# Production_Rev_A.net
KiCad netlist of a schematic drawn in EAGLE
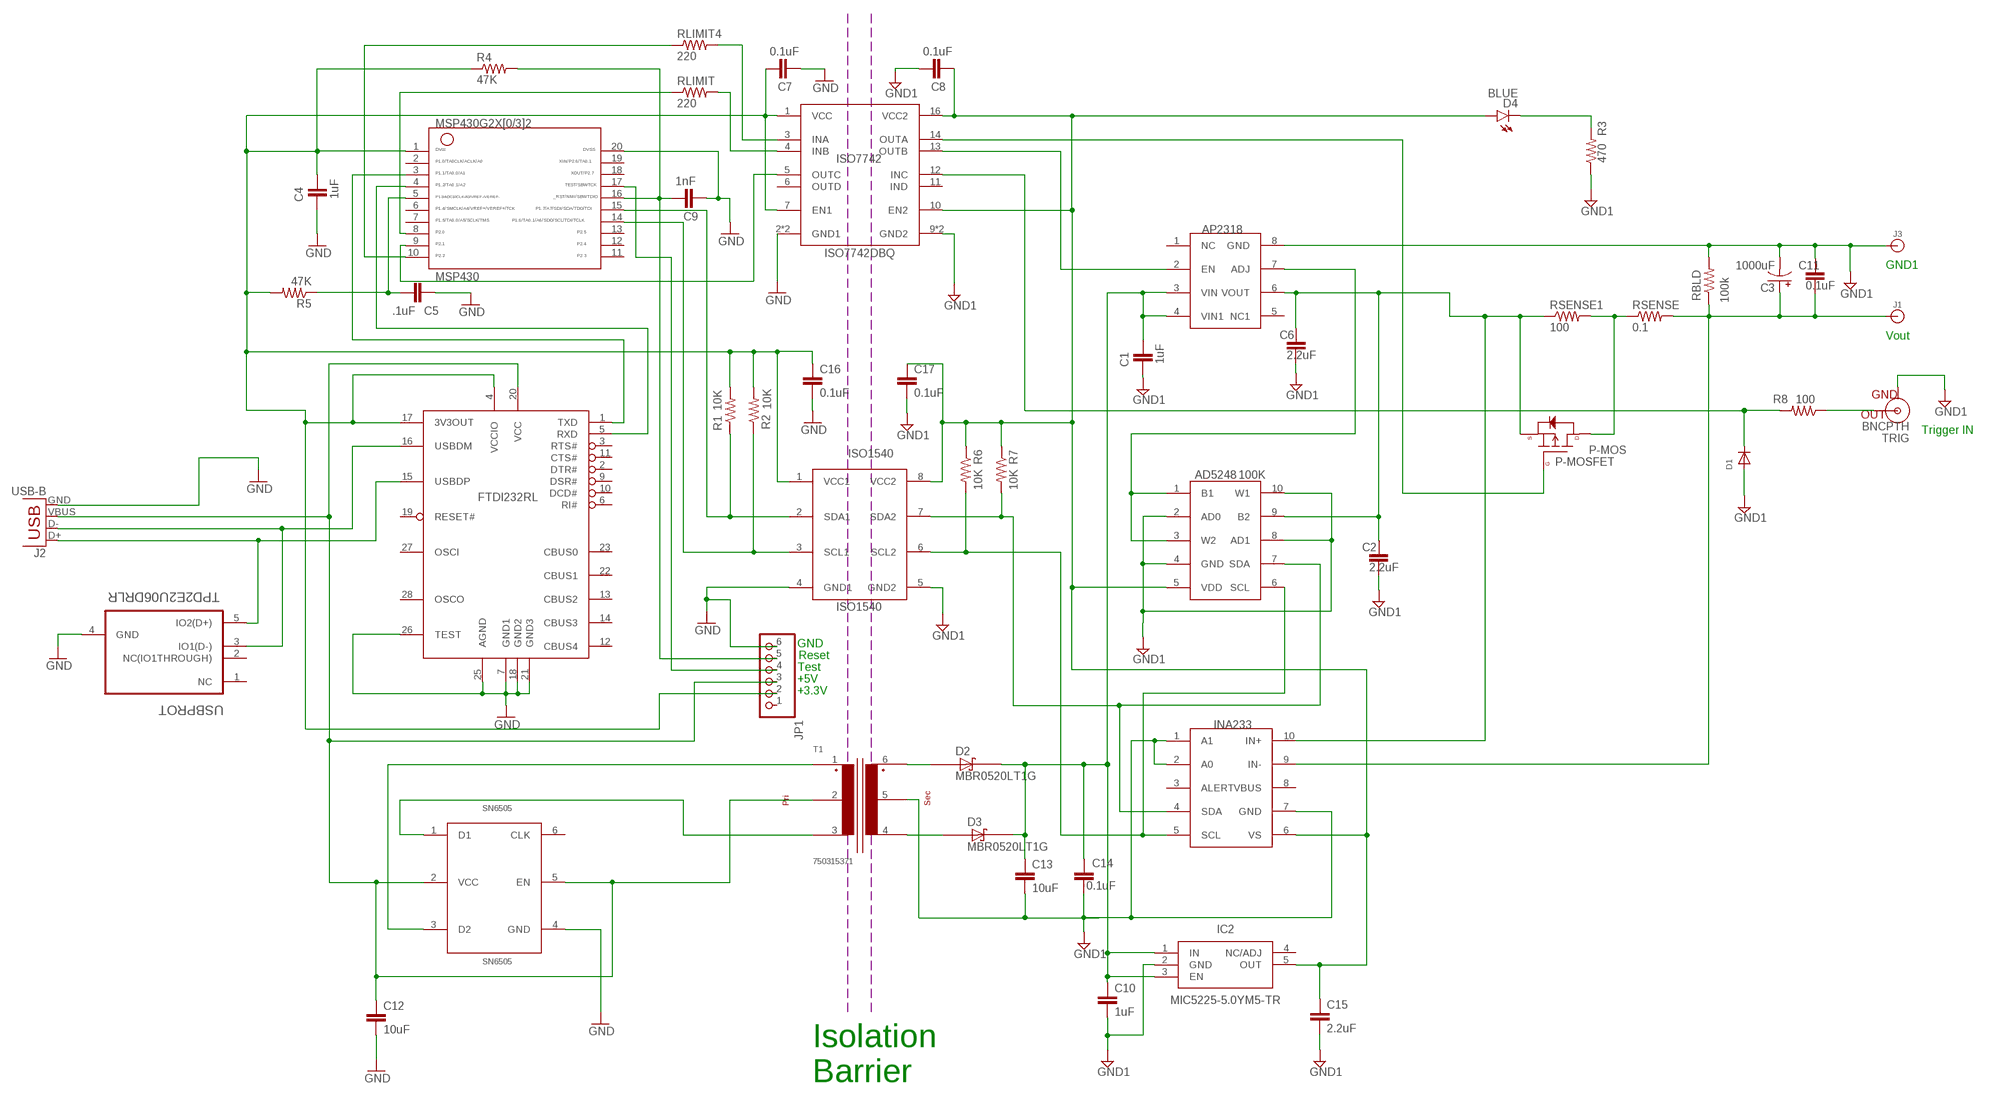
[diagram p0: schematic, sheet 1]

(export (version "E")
  (design (tool "Eeschema 10.0.6"))
  (components
    (comp (ref "AD5248")
      (value "100K")
      (footprint "eagle-import:MSOP-10")
      (libsource (lib "eagle-import") (part "AD5248"))
    )
    (comp (ref "AP2318")
      (value "AP2318")
      (footprint "eagle-import:SOIC-8")
      (libsource (lib "eagle-import") (part "AP2318"))
    )
    (comp (ref "C1")
      (value "1uF")
      (footprint "eagle-import:1206")
      (libsource (lib "eagle-import") (part "CAP1206"))
    )
    (comp (ref "C2")
      (value "2.2uF")
      (footprint "eagle-import:1206")
      (libsource (lib "eagle-import") (part "CAP1206"))
    )
    (comp (ref "C3")
      (value "1000uF")
      (footprint "eagle-import:PANASONIC_F")
      (libsource (lib "eagle-import") (part "CPOL-USF"))
    )
    (comp (ref "C4")
      (value "1uF")
      (footprint "eagle-import:1206")
      (libsource (lib "eagle-import") (part "CAP1206"))
    )
    (comp (ref "C5")
      (value ".1uF")
      (footprint "eagle-import:1206")
      (libsource (lib "eagle-import") (part "CAP1206"))
    )
    (comp (ref "C6")
      (value "2.2uF")
      (footprint "eagle-import:1206")
      (libsource (lib "eagle-import") (part "CAP1206"))
    )
    (comp (ref "C7")
      (value "0.1uF")
      (footprint "eagle-import:1206")
      (libsource (lib "eagle-import") (part "CAP1206"))
    )
    (comp (ref "C8")
      (value "0.1uF")
      (footprint "eagle-import:1206")
      (libsource (lib "eagle-import") (part "CAP1206"))
    )
    (comp (ref "C9")
      (value "1nF")
      (footprint "eagle-import:1206")
      (libsource (lib "eagle-import") (part "CAP1206"))
    )
    (comp (ref "C10")
      (value "1uF")
      (footprint "eagle-import:1206")
      (libsource (lib "eagle-import") (part "CAP1206"))
    )
    (comp (ref "C11")
      (value "0.1uF")
      (footprint "eagle-import:1206")
      (libsource (lib "eagle-import") (part "CAP1206"))
    )
    (comp (ref "C12")
      (value "10uF")
      (footprint "eagle-import:1206")
      (libsource (lib "eagle-import") (part "CAP1206"))
    )
    (comp (ref "C13")
      (value "10uF")
      (footprint "eagle-import:1206")
      (libsource (lib "eagle-import") (part "CAP1206"))
    )
    (comp (ref "C14")
      (value "0.1uF")
      (footprint "eagle-import:1206")
      (libsource (lib "eagle-import") (part "CAP1206"))
    )
    (comp (ref "C15")
      (value "2.2uF")
      (footprint "eagle-import:1206")
      (libsource (lib "eagle-import") (part "CAP1206"))
    )
    (comp (ref "C16")
      (value "0.1uF")
      (footprint "eagle-import:1206")
      (libsource (lib "eagle-import") (part "CAP1206"))
    )
    (comp (ref "C17")
      (value "0.1uF")
      (footprint "eagle-import:1206")
      (libsource (lib "eagle-import") (part "CAP1206"))
    )
    (comp (ref "D1")
      (value "DIODESOD-123")
      (footprint "eagle-import:SOD-123")
      (libsource (lib "eagle-import") (part "DIODESOD-123"))
    )
    (comp (ref "D2")
      (value "MBR0520LT1G")
      (footprint "eagle-import:SOD3716X117(SOD-123)")
      (fields (field (name "MF") "ON Semiconductor"))
      (libsource (lib "eagle-import") (part "MBR0520LT1G"))
    )
    (comp (ref "D3")
      (value "MBR0520LT1G")
      (footprint "eagle-import:SOD3716X117(SOD-123)")
      (fields (field (name "MF") "ON Semiconductor"))
      (libsource (lib "eagle-import") (part "MBR0520LT1G"))
    )
    (comp (ref "D4")
      (value "BLUE")
      (footprint "eagle-import:LED-1206")
      (libsource (lib "eagle-import") (part "LED-BLUE1206"))
    )
    (comp (ref "FTDI232RL")
      (value "FT232RL")
      (footprint "eagle-import:SSOP28DB")
      (libsource (lib "eagle-import") (part "FT232RL"))
    )
    (comp (ref "IC2")
      (value "MIC5225-5.0YM5-TR")
      (footprint "eagle-import:SOT95P280X130-5N")
      (fields (field (name "MF") "Microchip"))
      (libsource (lib "eagle-import") (part "MIC5225-5.0YM5-TR"))
    )
    (comp (ref "INA233")
      (value "INA233")
      (footprint "eagle-import:VSSOP-10")
      (libsource (lib "eagle-import") (part "INA233"))
    )
    (comp (ref "ISO1540")
      (value "ISO1540")
      (footprint "eagle-import:SOIC127P600X175-8N")
      (libsource (lib "eagle-import") (part "ISO1540"))
    )
    (comp (ref "ISO7742")
      (value "ISO7742DBQ")
      (footprint "eagle-import:SOP63P599X175-16N")
      (fields (field (name "MF") "Texas Instruments"))
      (libsource (lib "eagle-import") (part "ISO7742DBQ"))
    )
    (comp (ref "J1")
      (value "BANANA_CONN")
      (footprint "eagle-import:BANANA_CONN")
      (libsource (lib "eagle-import") (part "BANANA_CONN"))
    )
    (comp (ref "J2")
      (value "USB-B")
      (footprint "eagle-import:USB-B-PTH")
      (libsource (lib "eagle-import") (part "USBPTH"))
    )
    (comp (ref "J3")
      (value "BANANA_CONN")
      (footprint "eagle-import:BANANA_CONN")
      (libsource (lib "eagle-import") (part "BANANA_CONN"))
    )
    (comp (ref "JP1")
      (value "PINHD-1X6")
      (footprint "eagle-import:1X06")
      (libsource (lib "eagle-import") (part "PINHD-1X6"))
    )
    (comp (ref "MSP430")
      (value "MSP430")
      (footprint "eagle-import:PW20")
      (libsource (lib "eagle-import") (part "G2X[0/3]2---PW20"))
    )
    (comp (ref "P-MOS")
      (value "P-MOSFET")
      (footprint "eagle-import:SOT23-3")
      (libsource (lib "eagle-import") (part "P-CHANNEL-MOSFET"))
    )
    (comp (ref "R1")
      (value "10K")
      (footprint "eagle-import:1206")
      (libsource (lib "eagle-import") (part "RESISTOR1206"))
    )
    (comp (ref "R2")
      (value "10K")
      (footprint "eagle-import:1206")
      (libsource (lib "eagle-import") (part "RESISTOR1206"))
    )
    (comp (ref "R3")
      (value "470")
      (footprint "eagle-import:1206")
      (libsource (lib "eagle-import") (part "RESISTOR1206"))
    )
    (comp (ref "R4")
      (value "47K")
      (footprint "eagle-import:1206")
      (libsource (lib "eagle-import") (part "RESISTOR1206"))
    )
    (comp (ref "R5")
      (value "47K")
      (footprint "eagle-import:1206")
      (libsource (lib "eagle-import") (part "RESISTOR1206"))
    )
    (comp (ref "R6")
      (value "10K")
      (footprint "eagle-import:1206")
      (libsource (lib "eagle-import") (part "RESISTOR1206"))
    )
    (comp (ref "R7")
      (value "10K")
      (footprint "eagle-import:1206")
      (libsource (lib "eagle-import") (part "RESISTOR1206"))
    )
    (comp (ref "R8")
      (value "100")
      (footprint "eagle-import:1206")
      (libsource (lib "eagle-import") (part "RESISTOR1206"))
    )
    (comp (ref "RBLD")
      (value "100k")
      (footprint "eagle-import:1206")
      (libsource (lib "eagle-import") (part "RESISTOR1206"))
    )
    (comp (ref "RLIMIT")
      (value "220")
      (footprint "eagle-import:1206")
      (libsource (lib "eagle-import") (part "SparkFun-Resistors_RESISTOR1206"))
    )
    (comp (ref "RLIMIT4")
      (value "220")
      (footprint "eagle-import:1206")
      (libsource (lib "eagle-import") (part "SparkFun-Resistors_RESISTOR1206"))
    )
    (comp (ref "RSENSE")
      (value "0.1")
      (footprint "eagle-import:1206")
      (libsource (lib "eagle-import") (part "SparkFun-Resistors_RESISTOR1206"))
    )
    (comp (ref "RSENSE1")
      (value "100")
      (footprint "eagle-import:1206")
      (libsource (lib "eagle-import") (part "SparkFun-Resistors_RESISTOR1206"))
    )
    (comp (ref "SN6505")
      (value "SN6505")
      (footprint "eagle-import:SOT95P280X145-6N")
      (libsource (lib "eagle-import") (part "SN6505"))
    )
    (comp (ref "T1")
      (value "750315371")
      (footprint "eagle-import:TOR-6P-HT4_SMT_6PIN_(1201)")
      (fields (field (name "MF") "Wurth Electronics"))
      (libsource (lib "eagle-import") (part "750315371"))
    )
    (comp (ref "TRIG")
      (value "BNCPTH")
      (footprint "eagle-import:BNC")
      (libsource (lib "eagle-import") (part "BNCPTH"))
    )
    (comp (ref "USBPROT")
      (value "TPD2E2U06DRLR")
      (footprint "eagle-import:SOT50P160X60-5N")
      (fields (field (name "MF") "Texas Instruments"))
      (libsource (lib "eagle-import") (part "TPD2E2U06DRLR"))
    )
  )
  (nets
    (net (code "1") (name "/NC") (class "Default")
      (node (ref "USBPROT") (pin "1") (pinfunction "NC_1") (pintype "power_in"))
    )
    (net (code "2") (name "GND") (class "Default")
      (node (ref "C12") (pin "2") (pinfunction "2_2") (pintype "passive"))
      (node (ref "C16") (pin "2") (pinfunction "2_2") (pintype "passive"))
      (node (ref "C4") (pin "1") (pinfunction "1_1") (pintype "passive"))
      (node (ref "C5") (pin "1") (pinfunction "1_1") (pintype "passive"))
      (node (ref "C7") (pin "1") (pinfunction "1_1") (pintype "passive"))
      (node (ref "C9") (pin "1") (pinfunction "1_1") (pintype "passive"))
      (node (ref "FTDI232RL") (pin "18") (pinfunction "GND2_18") (pintype "power_in"))
      (node (ref "FTDI232RL") (pin "21") (pinfunction "GND3_21") (pintype "power_in"))
      (node (ref "FTDI232RL") (pin "25") (pinfunction "AGND_25") (pintype "power_in"))
      (node (ref "FTDI232RL") (pin "26") (pinfunction "TEST_26") (pintype "input"))
      (node (ref "FTDI232RL") (pin "7") (pinfunction "GND1_7") (pintype "power_in"))
      (node (ref "ISO1540") (pin "4") (pinfunction "GND1_4") (pintype "bidirectional"))
      (node (ref "ISO7742") (pin "2") (pinfunction "GND1_2") (pintype "power_in"))
      (node (ref "ISO7742") (pin "8") (pinfunction "GND1_8") (pintype "power_in"))
      (node (ref "J2") (pin "GND") (pinfunction "GND_GND") (pintype "bidirectional"))
      (node (ref "JP1") (pin "6") (pinfunction "6_6") (pintype "passive"))
      (node (ref "MSP430") (pin "20") (pinfunction "20_20") (pintype "bidirectional"))
      (node (ref "SN6505") (pin "4") (pinfunction "GND_4") (pintype "bidirectional"))
      (node (ref "USBPROT") (pin "4") (pinfunction "GND_4") (pintype "passive"))
    )
    (net (code "3") (name "GND1") (class "Default")
      (node (ref "AD5248") (pin "10") (pinfunction "W1_10") (pintype "bidirectional"))
      (node (ref "AD5248") (pin "2") (pinfunction "AD0_2") (pintype "bidirectional"))
      (node (ref "AD5248") (pin "4") (pinfunction "GND_4") (pintype "bidirectional"))
      (node (ref "AD5248") (pin "8") (pinfunction "AD1_8") (pintype "bidirectional"))
      (node (ref "AP2318") (pin "8") (pinfunction "GND_8") (pintype "bidirectional"))
      (node (ref "C1") (pin "1") (pinfunction "1_1") (pintype "passive"))
      (node (ref "C10") (pin "2") (pinfunction "2_2") (pintype "passive"))
      (node (ref "C11") (pin "1") (pinfunction "1_1") (pintype "passive"))
      (node (ref "C13") (pin "2") (pinfunction "2_2") (pintype "passive"))
      (node (ref "C14") (pin "2") (pinfunction "2_2") (pintype "passive"))
      (node (ref "C15") (pin "2") (pinfunction "2_2") (pintype "passive"))
      (node (ref "C17") (pin "2") (pinfunction "2_2") (pintype "passive"))
      (node (ref "C2") (pin "2") (pinfunction "2_2") (pintype "passive"))
      (node (ref "C3") (pin "-") (pinfunction "-_-") (pintype "passive"))
      (node (ref "C6") (pin "2") (pinfunction "2_2") (pintype "passive"))
      (node (ref "C8") (pin "2") (pinfunction "2_2") (pintype "passive"))
      (node (ref "D1") (pin "A") (pinfunction "A_A") (pintype "passive"))
      (node (ref "IC2") (pin "2") (pinfunction "GND_2") (pintype "passive"))
      (node (ref "INA233") (pin "1") (pinfunction "A1_1") (pintype "bidirectional"))
      (node (ref "INA233") (pin "2") (pinfunction "A0_2") (pintype "bidirectional"))
      (node (ref "INA233") (pin "7") (pinfunction "GND_7") (pintype "bidirectional"))
      (node (ref "ISO1540") (pin "5") (pinfunction "GND2_5") (pintype "bidirectional"))
      (node (ref "ISO7742") (pin "15") (pinfunction "GND2_15") (pintype "power_in"))
      (node (ref "ISO7742") (pin "9") (pinfunction "GND2_9") (pintype "power_in"))
      (node (ref "J3") (pin "P$1") (pinfunction "1_P$1") (pintype "passive"))
      (node (ref "R3") (pin "1") (pinfunction "1_1") (pintype "passive"))
      (node (ref "RBLD") (pin "2") (pinfunction "2_2") (pintype "passive"))
      (node (ref "T1") (pin "5") (pinfunction "5_5") (pintype "passive"))
      (node (ref "TRIG") (pin "GND") (pinfunction "GND_GND") (pintype "bidirectional"))
    )
    (net (code "4") (name "Net-(AD5248-B1)") (class "Default")
      (node (ref "AD5248") (pin "1") (pinfunction "B1_1") (pintype "bidirectional"))
      (node (ref "AD5248") (pin "3") (pinfunction "W2_3") (pintype "bidirectional"))
      (node (ref "AP2318") (pin "7") (pinfunction "ADJ_7") (pintype "bidirectional"))
    )
    (net (code "5") (name "Net-(AD5248-B2)") (class "Default")
      (node (ref "AD5248") (pin "9") (pinfunction "B2_9") (pintype "bidirectional"))
      (node (ref "AP2318") (pin "6") (pinfunction "VOUT_6") (pintype "bidirectional"))
      (node (ref "C2") (pin "1") (pinfunction "1_1") (pintype "passive"))
      (node (ref "C6") (pin "1") (pinfunction "1_1") (pintype "passive"))
      (node (ref "INA233") (pin "10") (pinfunction "IN+_10") (pintype "input"))
      (node (ref "P-MOS") (pin "2") (pinfunction "S_2") (pintype "passive"))
      (node (ref "RSENSE1") (pin "1") (pinfunction "1_1") (pintype "passive"))
    )
    (net (code "6") (name "Net-(AD5248-SCL)") (class "Default")
      (node (ref "AD5248") (pin "6") (pinfunction "SCL_6") (pintype "input"))
      (node (ref "INA233") (pin "5") (pinfunction "SCL_5") (pintype "input"))
      (node (ref "ISO1540") (pin "6") (pinfunction "SCL2_6") (pintype "bidirectional"))
      (node (ref "R6") (pin "2") (pinfunction "2_2") (pintype "passive"))
    )
    (net (code "7") (name "Net-(AD5248-SDA)") (class "Default")
      (node (ref "AD5248") (pin "7") (pinfunction "SDA_7") (pintype "input"))
      (node (ref "INA233") (pin "4") (pinfunction "SDA_4") (pintype "input"))
      (node (ref "ISO1540") (pin "7") (pinfunction "SDA2_7") (pintype "bidirectional"))
      (node (ref "R7") (pin "2") (pinfunction "2_2") (pintype "passive"))
    )
    (net (code "8") (name "Net-(AD5248-VDD)") (class "Default")
      (node (ref "AD5248") (pin "5") (pinfunction "VDD_5") (pintype "power_in"))
      (node (ref "C15") (pin "1") (pinfunction "1_1") (pintype "passive"))
      (node (ref "C17") (pin "1") (pinfunction "1_1") (pintype "passive"))
      (node (ref "C8") (pin "1") (pinfunction "1_1") (pintype "passive"))
      (node (ref "D4") (pin "A") (pinfunction "A_A") (pintype "passive"))
      (node (ref "IC2") (pin "5") (pinfunction "OUT_5") (pintype "passive"))
      (node (ref "INA233") (pin "6") (pinfunction "VS_6") (pintype "power_in"))
      (node (ref "ISO1540") (pin "8") (pinfunction "VCC2_8") (pintype "bidirectional"))
      (node (ref "ISO7742") (pin "10") (pinfunction "EN2_10") (pintype "input"))
      (node (ref "ISO7742") (pin "16") (pinfunction "VCC2_16") (pintype "power_in"))
      (node (ref "R6") (pin "1") (pinfunction "1_1") (pintype "passive"))
      (node (ref "R7") (pin "1") (pinfunction "1_1") (pintype "passive"))
    )
    (net (code "9") (name "Net-(AP2318-EN)") (class "Default")
      (node (ref "AP2318") (pin "2") (pinfunction "EN_2") (pintype "bidirectional"))
      (node (ref "ISO7742") (pin "13") (pinfunction "OUTB_13") (pintype "output"))
    )
    (net (code "10") (name "Net-(AP2318-VIN)") (class "Default")
      (node (ref "AP2318") (pin "3") (pinfunction "VIN_3") (pintype "power_in"))
      (node (ref "AP2318") (pin "4") (pinfunction "VIN1_4") (pintype "power_in"))
      (node (ref "C1") (pin "2") (pinfunction "2_2") (pintype "passive"))
      (node (ref "C10") (pin "1") (pinfunction "1_1") (pintype "passive"))
      (node (ref "C13") (pin "1") (pinfunction "1_1") (pintype "passive"))
      (node (ref "C14") (pin "1") (pinfunction "1_1") (pintype "passive"))
      (node (ref "D2") (pin "1") (pinfunction "C_1") (pintype "passive"))
      (node (ref "D3") (pin "1") (pinfunction "C_1") (pintype "passive"))
      (node (ref "IC2") (pin "1") (pinfunction "IN_1") (pintype "passive"))
      (node (ref "IC2") (pin "3") (pinfunction "EN_3") (pintype "passive"))
    )
    (net (code "11") (name "Net-(C5-Pad2)") (class "Default")
      (node (ref "C5") (pin "2") (pinfunction "2_2") (pintype "passive"))
      (node (ref "MSP430") (pin "5") (pinfunction "5_5") (pintype "bidirectional"))
      (node (ref "R5") (pin "1") (pinfunction "1_1") (pintype "passive"))
    )
    (net (code "12") (name "Net-(C9-Pad2)") (class "Default")
      (node (ref "C9") (pin "2") (pinfunction "2_2") (pintype "passive"))
      (node (ref "JP1") (pin "5") (pinfunction "5_5") (pintype "passive"))
      (node (ref "MSP430") (pin "16") (pinfunction "16_16") (pintype "bidirectional"))
      (node (ref "R4") (pin "2") (pinfunction "2_2") (pintype "passive"))
    )
    (net (code "13") (name "Net-(D2-A)") (class "Default")
      (node (ref "D2") (pin "2") (pinfunction "A_2") (pintype "passive"))
      (node (ref "T1") (pin "6") (pinfunction "6_6") (pintype "passive"))
    )
    (net (code "14") (name "Net-(D3-A)") (class "Default")
      (node (ref "D3") (pin "2") (pinfunction "A_2") (pintype "passive"))
      (node (ref "T1") (pin "4") (pinfunction "4_4") (pintype "passive"))
    )
    (net (code "15") (name "Net-(D4-PadC)") (class "Default")
      (node (ref "D4") (pin "C") (pinfunction "C_C") (pintype "passive"))
      (node (ref "R3") (pin "2") (pinfunction "2_2") (pintype "passive"))
    )
    (net (code "16") (name "Net-(FTDI232RL-3V3OUT)") (class "Default")
      (node (ref "C16") (pin "1") (pinfunction "1_1") (pintype "passive"))
      (node (ref "C4") (pin "2") (pinfunction "2_2") (pintype "passive"))
      (node (ref "C7") (pin "2") (pinfunction "2_2") (pintype "passive"))
      (node (ref "FTDI232RL") (pin "17") (pinfunction "3V3OUT_17") (pintype "output"))
      (node (ref "FTDI232RL") (pin "4") (pinfunction "VCCIO_4") (pintype "power_in"))
      (node (ref "ISO1540") (pin "1") (pinfunction "VCC1_1") (pintype "bidirectional"))
      (node (ref "ISO7742") (pin "1") (pinfunction "VCC_1") (pintype "power_in"))
      (node (ref "ISO7742") (pin "7") (pinfunction "EN1_7") (pintype "input"))
      (node (ref "JP1") (pin "2") (pinfunction "2_2") (pintype "passive"))
      (node (ref "MSP430") (pin "1") (pinfunction "1_1") (pintype "bidirectional"))
      (node (ref "R1") (pin "2") (pinfunction "2_2") (pintype "passive"))
      (node (ref "R2") (pin "2") (pinfunction "2_2") (pintype "passive"))
      (node (ref "R4") (pin "1") (pinfunction "1_1") (pintype "passive"))
      (node (ref "R5") (pin "2") (pinfunction "2_2") (pintype "passive"))
    )
    (net (code "17") (name "Net-(FTDI232RL-RXD)") (class "Default")
      (node (ref "FTDI232RL") (pin "5") (pinfunction "RXD_5") (pintype "input"))
      (node (ref "MSP430") (pin "4") (pinfunction "4_4") (pintype "bidirectional"))
    )
    (net (code "18") (name "Net-(FTDI232RL-TXD)") (class "Default")
      (node (ref "FTDI232RL") (pin "1") (pinfunction "TXD_1") (pintype "output"))
      (node (ref "MSP430") (pin "3") (pinfunction "3_3") (pintype "bidirectional"))
    )
    (net (code "19") (name "Net-(FTDI232RL-USBDM)") (class "Default")
      (node (ref "FTDI232RL") (pin "16") (pinfunction "USBDM_16") (pintype "bidirectional"))
      (node (ref "J2") (pin "D-") (pinfunction "D-_D-") (pintype "bidirectional"))
      (node (ref "USBPROT") (pin "3") (pinfunction "IO1(D-)_3") (pintype "bidirectional"))
    )
    (net (code "20") (name "Net-(FTDI232RL-USBDP)") (class "Default")
      (node (ref "FTDI232RL") (pin "15") (pinfunction "USBDP_15") (pintype "bidirectional"))
      (node (ref "J2") (pin "D+") (pinfunction "D+_D+") (pintype "bidirectional"))
      (node (ref "USBPROT") (pin "5") (pinfunction "IO2(D+)_5") (pintype "bidirectional"))
    )
    (net (code "21") (name "Net-(FTDI232RL-VCC)") (class "Default")
      (node (ref "C12") (pin "1") (pinfunction "1_1") (pintype "passive"))
      (node (ref "FTDI232RL") (pin "20") (pinfunction "VCC_20") (pintype "power_in"))
      (node (ref "J2") (pin "VBUS") (pinfunction "VBUS_VBUS") (pintype "bidirectional"))
      (node (ref "JP1") (pin "3") (pinfunction "3_3") (pintype "passive"))
      (node (ref "SN6505") (pin "2") (pinfunction "VCC_2") (pintype "bidirectional"))
      (node (ref "SN6505") (pin "5") (pinfunction "EN_5") (pintype "bidirectional"))
      (node (ref "T1") (pin "2") (pinfunction "2_2") (pintype "passive"))
    )
    (net (code "22") (name "Net-(INA233-IN-)") (class "Default")
      (node (ref "C11") (pin "2") (pinfunction "2_2") (pintype "passive"))
      (node (ref "C3") (pin "+") (pinfunction "+_+") (pintype "passive"))
      (node (ref "INA233") (pin "9") (pinfunction "IN-_9") (pintype "input"))
      (node (ref "J1") (pin "P$1") (pinfunction "1_P$1") (pintype "passive"))
      (node (ref "RBLD") (pin "1") (pinfunction "1_1") (pintype "passive"))
      (node (ref "RSENSE") (pin "2") (pinfunction "2_2") (pintype "passive"))
    )
    (net (code "23") (name "Net-(ISO1540-SCL1)") (class "Default")
      (node (ref "ISO1540") (pin "3") (pinfunction "SCL1_3") (pintype "bidirectional"))
      (node (ref "MSP430") (pin "14") (pinfunction "14_14") (pintype "bidirectional"))
      (node (ref "R2") (pin "1") (pinfunction "1_1") (pintype "passive"))
    )
    (net (code "24") (name "Net-(ISO1540-SDA1)") (class "Default")
      (node (ref "ISO1540") (pin "2") (pinfunction "SDA1_2") (pintype "bidirectional"))
      (node (ref "MSP430") (pin "15") (pinfunction "15_15") (pintype "bidirectional"))
      (node (ref "R1") (pin "1") (pinfunction "1_1") (pintype "passive"))
    )
    (net (code "25") (name "Net-(ISO7742-INA)") (class "Default")
      (node (ref "ISO7742") (pin "3") (pinfunction "INA_3") (pintype "input"))
      (node (ref "RLIMIT4") (pin "2") (pinfunction "2_2") (pintype "passive"))
    )
    (net (code "26") (name "Net-(ISO7742-INB)") (class "Default")
      (node (ref "ISO7742") (pin "4") (pinfunction "INB_4") (pintype "input"))
      (node (ref "RLIMIT") (pin "2") (pinfunction "2_2") (pintype "passive"))
    )
    (net (code "27") (name "Net-(ISO7742-INC)") (class "Default")
      (node (ref "D1") (pin "C") (pinfunction "C_C") (pintype "passive"))
      (node (ref "ISO7742") (pin "12") (pinfunction "INC_12") (pintype "input"))
      (node (ref "R8") (pin "2") (pinfunction "2_2") (pintype "passive"))
    )
    (net (code "28") (name "Net-(ISO7742-OUTA)") (class "Default")
      (node (ref "ISO7742") (pin "14") (pinfunction "OUTA_14") (pintype "output"))
      (node (ref "P-MOS") (pin "1") (pinfunction "G_1") (pintype "passive"))
    )
    (net (code "29") (name "Net-(ISO7742-OUTC)") (class "Default")
      (node (ref "ISO7742") (pin "5") (pinfunction "OUTC_5") (pintype "output"))
      (node (ref "MSP430") (pin "9") (pinfunction "9_9") (pintype "bidirectional"))
    )
    (net (code "30") (name "Net-(JP1-Pad4)") (class "Default")
      (node (ref "JP1") (pin "4") (pinfunction "4_4") (pintype "passive"))
      (node (ref "MSP430") (pin "17") (pinfunction "17_17") (pintype "bidirectional"))
    )
    (net (code "31") (name "Net-(MSP430-Pad8)") (class "Default")
      (node (ref "MSP430") (pin "8") (pinfunction "8_8") (pintype "bidirectional"))
      (node (ref "RLIMIT") (pin "1") (pinfunction "1_1") (pintype "passive"))
    )
    (net (code "32") (name "Net-(MSP430-Pad10)") (class "Default")
      (node (ref "MSP430") (pin "10") (pinfunction "10_10") (pintype "bidirectional"))
      (node (ref "RLIMIT4") (pin "1") (pinfunction "1_1") (pintype "passive"))
    )
    (net (code "33") (name "Net-(P-MOS-D)") (class "Default")
      (node (ref "P-MOS") (pin "3") (pinfunction "D_3") (pintype "passive"))
      (node (ref "RSENSE") (pin "1") (pinfunction "1_1") (pintype "passive"))
      (node (ref "RSENSE1") (pin "2") (pinfunction "2_2") (pintype "passive"))
    )
    (net (code "34") (name "Net-(SN6505-D1)") (class "Default")
      (node (ref "SN6505") (pin "1") (pinfunction "D1_1") (pintype "bidirectional"))
      (node (ref "T1") (pin "3") (pinfunction "3_3") (pintype "passive"))
    )
    (net (code "35") (name "Net-(SN6505-D2)") (class "Default")
      (node (ref "SN6505") (pin "3") (pinfunction "D2_3") (pintype "bidirectional"))
      (node (ref "T1") (pin "1") (pinfunction "1_1") (pintype "passive"))
    )
    (net (code "36") (name "Net-(TRIG-OUT)") (class "Default")
      (node (ref "R8") (pin "1") (pinfunction "1_1") (pintype "passive"))
      (node (ref "TRIG") (pin "S") (pinfunction "OUT_S") (pintype "bidirectional"))
    )
    (net (code "37") (name "unconnected-(AP2318-NC-Pad1)") (class "Default")
      (node (ref "AP2318") (pin "1") (pinfunction "NC_1") (pintype "no_connect"))
    )
    (net (code "38") (name "unconnected-(AP2318-NC1-Pad5)") (class "Default")
      (node (ref "AP2318") (pin "5") (pinfunction "NC1_5") (pintype "no_connect"))
    )
    (net (code "39") (name "unconnected-(FTDI232RL-CBUS0-Pad23)") (class "Default")
      (node (ref "FTDI232RL") (pin "23") (pinfunction "CBUS0_23") (pintype "bidirectional"))
    )
    (net (code "40") (name "unconnected-(FTDI232RL-CBUS1-Pad22)") (class "Default")
      (node (ref "FTDI232RL") (pin "22") (pinfunction "CBUS1_22") (pintype "bidirectional"))
    )
    (net (code "41") (name "unconnected-(FTDI232RL-CBUS2-Pad13)") (class "Default")
      (node (ref "FTDI232RL") (pin "13") (pinfunction "CBUS2_13") (pintype "bidirectional"))
    )
    (net (code "42") (name "unconnected-(FTDI232RL-CBUS3-Pad14)") (class "Default")
      (node (ref "FTDI232RL") (pin "14") (pinfunction "CBUS3_14") (pintype "bidirectional"))
    )
    (net (code "43") (name "unconnected-(FTDI232RL-CBUS4-Pad12)") (class "Default")
      (node (ref "FTDI232RL") (pin "12") (pinfunction "CBUS4_12") (pintype "bidirectional"))
    )
    (net (code "44") (name "unconnected-(FTDI232RL-CTS#-Pad11)") (class "Default")
      (node (ref "FTDI232RL") (pin "11") (pinfunction "CTS#_11") (pintype "input"))
    )
    (net (code "45") (name "unconnected-(FTDI232RL-DCD#-Pad10)") (class "Default")
      (node (ref "FTDI232RL") (pin "10") (pinfunction "DCD#_10") (pintype "input"))
    )
    (net (code "46") (name "unconnected-(FTDI232RL-DSR#-Pad9)") (class "Default")
      (node (ref "FTDI232RL") (pin "9") (pinfunction "DSR#_9") (pintype "input"))
    )
    (net (code "47") (name "unconnected-(FTDI232RL-DTR#-Pad2)") (class "Default")
      (node (ref "FTDI232RL") (pin "2") (pinfunction "DTR#_2") (pintype "output"))
    )
    (net (code "48") (name "unconnected-(FTDI232RL-OSCI-Pad27)") (class "Default")
      (node (ref "FTDI232RL") (pin "27") (pinfunction "OSCI_27") (pintype "input"))
    )
    (net (code "49") (name "unconnected-(FTDI232RL-OSCO-Pad28)") (class "Default")
      (node (ref "FTDI232RL") (pin "28") (pinfunction "OSCO_28") (pintype "output"))
    )
    (net (code "50") (name "unconnected-(FTDI232RL-RESET#-Pad19)") (class "Default")
      (node (ref "FTDI232RL") (pin "19") (pinfunction "RESET#_19") (pintype "input"))
    )
    (net (code "51") (name "unconnected-(FTDI232RL-RI#-Pad6)") (class "Default")
      (node (ref "FTDI232RL") (pin "6") (pinfunction "RI#_6") (pintype "input"))
    )
    (net (code "52") (name "unconnected-(FTDI232RL-RTS#-Pad3)") (class "Default")
      (node (ref "FTDI232RL") (pin "3") (pinfunction "RTS#_3") (pintype "output"))
    )
    (net (code "53") (name "unconnected-(IC2-NC{slash}ADJ-Pad4)") (class "Default")
      (node (ref "IC2") (pin "4") (pinfunction "NC/ADJ_4") (pintype "passive"))
    )
    (net (code "54") (name "unconnected-(INA233-ALERT-Pad3)") (class "Default")
      (node (ref "INA233") (pin "3") (pinfunction "ALERT_3") (pintype "input"))
    )
    (net (code "55") (name "unconnected-(INA233-VBUS-Pad8)") (class "Default")
      (node (ref "INA233") (pin "8") (pinfunction "VBUS_8") (pintype "bidirectional"))
    )
    (net (code "56") (name "unconnected-(ISO7742-IND-Pad11)") (class "Default")
      (node (ref "ISO7742") (pin "11") (pinfunction "IND_11") (pintype "input"))
    )
    (net (code "57") (name "unconnected-(ISO7742-OUTD-Pad6)") (class "Default")
      (node (ref "ISO7742") (pin "6") (pinfunction "OUTD_6") (pintype "output"))
    )
    (net (code "58") (name "unconnected-(JP1-Pad1)") (class "Default")
      (node (ref "JP1") (pin "1") (pinfunction "1_1") (pintype "passive"))
    )
    (net (code "59") (name "unconnected-(MSP430-Pad2)") (class "Default")
      (node (ref "MSP430") (pin "2") (pinfunction "2_2") (pintype "bidirectional"))
    )
    (net (code "60") (name "unconnected-(MSP430-Pad6)") (class "Default")
      (node (ref "MSP430") (pin "6") (pinfunction "6_6") (pintype "bidirectional"))
    )
    (net (code "61") (name "unconnected-(MSP430-Pad7)") (class "Default")
      (node (ref "MSP430") (pin "7") (pinfunction "7_7") (pintype "bidirectional"))
    )
    (net (code "62") (name "unconnected-(MSP430-Pad11)") (class "Default")
      (node (ref "MSP430") (pin "11") (pinfunction "11_11") (pintype "bidirectional"))
    )
    (net (code "63") (name "unconnected-(MSP430-Pad12)") (class "Default")
      (node (ref "MSP430") (pin "12") (pinfunction "12_12") (pintype "bidirectional"))
    )
    (net (code "64") (name "unconnected-(MSP430-Pad13)") (class "Default")
      (node (ref "MSP430") (pin "13") (pinfunction "13_13") (pintype "bidirectional"))
    )
    (net (code "65") (name "unconnected-(MSP430-Pad18)") (class "Default")
      (node (ref "MSP430") (pin "18") (pinfunction "18_18") (pintype "bidirectional"))
    )
    (net (code "66") (name "unconnected-(MSP430-Pad19)") (class "Default")
      (node (ref "MSP430") (pin "19") (pinfunction "19_19") (pintype "bidirectional"))
    )
    (net (code "67") (name "unconnected-(SN6505-CLK-Pad6)") (class "Default")
      (node (ref "SN6505") (pin "6") (pinfunction "CLK_6") (pintype "bidirectional"))
    )
    (net (code "68") (name "unconnected-(USBPROT-NC(IO1THROUGH)-Pad2)") (class "Default")
      (node (ref "USBPROT") (pin "2") (pinfunction "NC(IO1THROUGH)_2") (pintype "no_connect"))
    )
  )
)
